# FollowMe.net
KiCad netlist of a schematic drawn in EAGLE
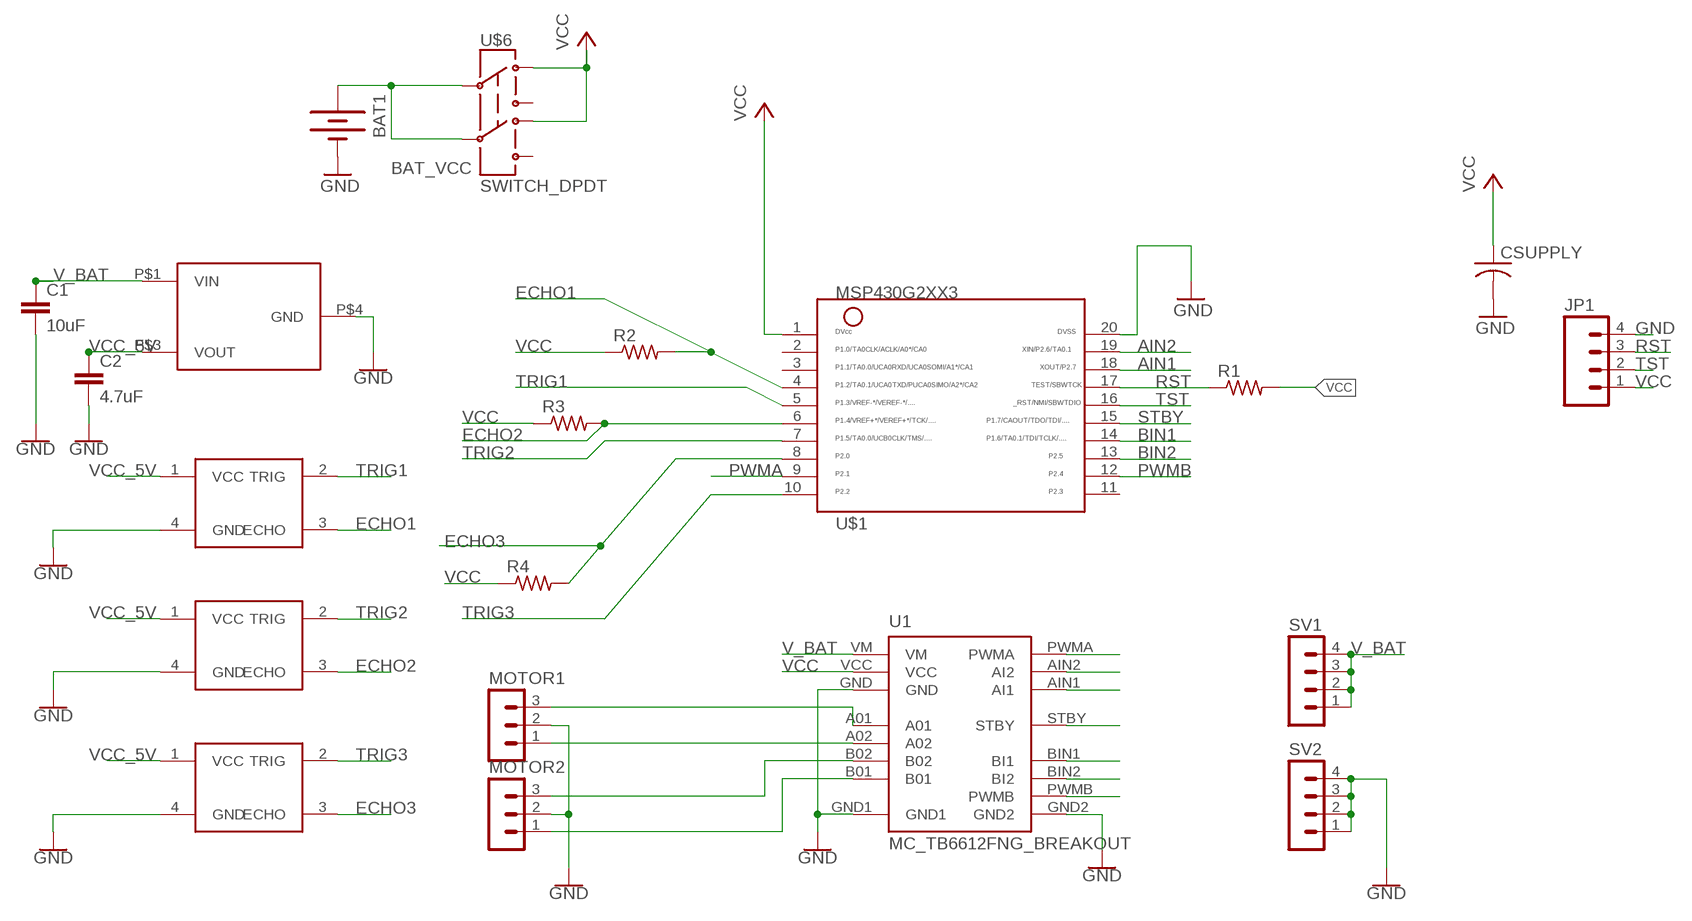
[diagram p0: schematic, sheet 1]

(export (version "E")
  (design (tool "Eeschema 10.0.6"))
  (components
    (comp (ref "BAT1")
      (value "BATTERY")
      (footprint "eagle-import:BATTERY_PACK_2AA")
      (libsource (lib "eagle-import") (part "BATTERY"))
    )
    (comp (ref "C1")
      (value "10uF")
      (footprint "eagle-import:1206")
      (libsource (lib "eagle-import") (part "10UF-1206-6.3V-20%"))
    )
    (comp (ref "C2")
      (value "4.7uF")
      (footprint "eagle-import:1206")
      (libsource (lib "eagle-import") (part "10UF-1206-6.3V-20%"))
    )
    (comp (ref "CSUPPLY")
      (value "C-USC1206")
      (footprint "eagle-import:C1206")
      (libsource (lib "eagle-import") (part "C-USC1206"))
    )
    (comp (ref "JP1")
      (value "M04LOCK")
      (footprint "eagle-import:1X04_LOCK")
      (libsource (lib "eagle-import") (part "M04LOCK"))
    )
    (comp (ref "MOTOR1")
      (value "MA03-1")
      (footprint "eagle-import:MA03-1")
      (libsource (lib "eagle-import") (part "MA03-1"))
    )
    (comp (ref "MOTOR2")
      (value "MA03-1")
      (footprint "eagle-import:MA03-1")
      (libsource (lib "eagle-import") (part "MA03-1"))
    )
    (comp (ref "R1")
      (value "R-US_R1206")
      (footprint "eagle-import:R1206")
      (libsource (lib "eagle-import") (part "R-US_R1206"))
    )
    (comp (ref "R2")
      (value "R-US_R1206")
      (footprint "eagle-import:R1206")
      (libsource (lib "eagle-import") (part "R-US_R1206"))
    )
    (comp (ref "R3")
      (value "R-US_R1206")
      (footprint "eagle-import:R1206")
      (libsource (lib "eagle-import") (part "R-US_R1206"))
    )
    (comp (ref "R4")
      (value "R-US_R1206")
      (footprint "eagle-import:R1206")
      (libsource (lib "eagle-import") (part "R-US_R1206"))
    )
    (comp (ref "SV1")
      (value "MA04-1")
      (footprint "eagle-import:MA04-1")
      (libsource (lib "eagle-import") (part "MA04-1"))
    )
    (comp (ref "SV2")
      (value "MA04-1")
      (footprint "eagle-import:MA04-1")
      (libsource (lib "eagle-import") (part "MA04-1"))
    )
    (comp (ref "U$1")
      (value "MSP430G2XX3TSSOP")
      (footprint "eagle-import:PW20")
      (libsource (lib "eagle-import") (part "MSP430G2XX3TSSOP"))
    )
    (comp (ref "U$2")
      (value "LDO")
      (footprint "eagle-import:LDO")
      (libsource (lib "eagle-import") (part "LDO"))
    )
    (comp (ref "U$3")
      (value "ULTRASONIC")
      (footprint "eagle-import:ULTRASONIC")
      (libsource (lib "eagle-import") (part "ULTRASONIC"))
    )
    (comp (ref "U$4")
      (value "ULTRASONIC")
      (footprint "eagle-import:ULTRASONIC")
      (libsource (lib "eagle-import") (part "ULTRASONIC"))
    )
    (comp (ref "U$5")
      (value "ULTRASONIC")
      (footprint "eagle-import:ULTRASONIC")
      (libsource (lib "eagle-import") (part "ULTRASONIC"))
    )
    (comp (ref "U$6")
      (value "SWITCH_DPDT")
      (footprint "eagle-import:JS_DPDT_TH")
      (libsource (lib "eagle-import") (part "SWITCH_DPDT"))
    )
    (comp (ref "U1")
      (value "MC_TB6612FNG_BREAKOUT")
      (footprint "eagle-import:MC_TB6612FNG")
      (libsource (lib "eagle-import") (part "MC_TB6612FNG_BREAKOUT"))
    )
  )
  (nets
    (net (code "1") (name "/AIN1") (class "Default")
      (node (ref "U$1") (pin "18") (pinfunction "18_18") (pintype "bidirectional"))
      (node (ref "U1") (pin "AIN1") (pinfunction "AI1_AIN1") (pintype "bidirectional"))
    )
    (net (code "2") (name "/AIN2") (class "Default")
      (node (ref "U$1") (pin "19") (pinfunction "19_19") (pintype "bidirectional"))
      (node (ref "U1") (pin "AIN2") (pinfunction "AI2_AIN2") (pintype "bidirectional"))
    )
    (net (code "3") (name "/BAT_VCC") (class "Default")
      (node (ref "BAT1") (pin "3V") (pinfunction "+_3V") (pintype "power_in"))
      (node (ref "U$6") (pin "2") (pinfunction "2_2") (pintype "bidirectional"))
      (node (ref "U$6") (pin "5") (pinfunction "5_5") (pintype "bidirectional"))
    )
    (net (code "4") (name "/BIN1") (class "Default")
      (node (ref "U$1") (pin "14") (pinfunction "14_14") (pintype "bidirectional"))
      (node (ref "U1") (pin "BIN1") (pinfunction "BI1_BIN1") (pintype "bidirectional"))
    )
    (net (code "5") (name "/BIN2") (class "Default")
      (node (ref "U$1") (pin "13") (pinfunction "13_13") (pintype "bidirectional"))
      (node (ref "U1") (pin "BIN2") (pinfunction "BI2_BIN2") (pintype "bidirectional"))
    )
    (net (code "6") (name "/ECHO1") (class "Default")
      (node (ref "R2") (pin "2") (pinfunction "2_2") (pintype "passive"))
      (node (ref "U$1") (pin "4") (pinfunction "4_4") (pintype "bidirectional"))
      (node (ref "U$3") (pin "3") (pinfunction "ECHO_3") (pintype "bidirectional"))
    )
    (net (code "7") (name "/ECHO2") (class "Default")
      (node (ref "R3") (pin "2") (pinfunction "2_2") (pintype "passive"))
      (node (ref "U$1") (pin "6") (pinfunction "6_6") (pintype "bidirectional"))
      (node (ref "U$4") (pin "3") (pinfunction "ECHO_3") (pintype "bidirectional"))
    )
    (net (code "8") (name "/ECHO3") (class "Default")
      (node (ref "R4") (pin "2") (pinfunction "2_2") (pintype "passive"))
      (node (ref "U$1") (pin "8") (pinfunction "8_8") (pintype "bidirectional"))
      (node (ref "U$5") (pin "3") (pinfunction "ECHO_3") (pintype "bidirectional"))
    )
    (net (code "9") (name "/PWMA") (class "Default")
      (node (ref "U$1") (pin "9") (pinfunction "9_9") (pintype "bidirectional"))
      (node (ref "U1") (pin "PWMA") (pinfunction "PWMA_PWMA") (pintype "bidirectional"))
    )
    (net (code "10") (name "/PWMB") (class "Default")
      (node (ref "U$1") (pin "12") (pinfunction "12_12") (pintype "bidirectional"))
      (node (ref "U1") (pin "PWMB") (pinfunction "PWMB_PWMB") (pintype "bidirectional"))
    )
    (net (code "11") (name "/RST") (class "Default")
      (node (ref "JP1") (pin "3") (pinfunction "3_3") (pintype "passive"))
      (node (ref "R1") (pin "1") (pinfunction "1_1") (pintype "passive"))
      (node (ref "U$1") (pin "17") (pinfunction "17_17") (pintype "bidirectional"))
    )
    (net (code "12") (name "/STBY") (class "Default")
      (node (ref "U$1") (pin "15") (pinfunction "15_15") (pintype "bidirectional"))
      (node (ref "U1") (pin "STBY") (pinfunction "STBY_STBY") (pintype "bidirectional"))
    )
    (net (code "13") (name "/TRIG1") (class "Default")
      (node (ref "U$1") (pin "5") (pinfunction "5_5") (pintype "bidirectional"))
      (node (ref "U$3") (pin "2") (pinfunction "TRIG_2") (pintype "bidirectional"))
    )
    (net (code "14") (name "/TRIG2") (class "Default")
      (node (ref "U$1") (pin "7") (pinfunction "7_7") (pintype "bidirectional"))
      (node (ref "U$4") (pin "2") (pinfunction "TRIG_2") (pintype "bidirectional"))
    )
    (net (code "15") (name "/TRIG3") (class "Default")
      (node (ref "U$1") (pin "10") (pinfunction "10_10") (pintype "bidirectional"))
      (node (ref "U$5") (pin "2") (pinfunction "TRIG_2") (pintype "bidirectional"))
    )
    (net (code "16") (name "/TST") (class "Default")
      (node (ref "JP1") (pin "2") (pinfunction "2_2") (pintype "passive"))
      (node (ref "U$1") (pin "16") (pinfunction "16_16") (pintype "bidirectional"))
    )
    (net (code "17") (name "/VCC_5V") (class "Default")
      (node (ref "C2") (pin "1") (pinfunction "1_1") (pintype "passive"))
      (node (ref "U$2") (pin "P$3") (pinfunction "VOUT_P$3") (pintype "bidirectional"))
      (node (ref "U$3") (pin "1") (pinfunction "VCC_1") (pintype "bidirectional"))
      (node (ref "U$4") (pin "1") (pinfunction "VCC_1") (pintype "bidirectional"))
      (node (ref "U$5") (pin "1") (pinfunction "VCC_1") (pintype "bidirectional"))
    )
    (net (code "18") (name "/V_BAT") (class "Default")
      (node (ref "C1") (pin "1") (pinfunction "1_1") (pintype "passive"))
      (node (ref "SV1") (pin "1") (pinfunction "1_1") (pintype "passive"))
      (node (ref "SV1") (pin "2") (pinfunction "2_2") (pintype "passive"))
      (node (ref "SV1") (pin "3") (pinfunction "3_3") (pintype "passive"))
      (node (ref "SV1") (pin "4") (pinfunction "4_4") (pintype "passive"))
      (node (ref "U$2") (pin "P$1") (pinfunction "VIN_P$1") (pintype "bidirectional"))
      (node (ref "U1") (pin "VM") (pinfunction "VM_VM") (pintype "bidirectional"))
    )
    (net (code "19") (name "GND") (class "Default")
      (node (ref "BAT1") (pin "GND") (pinfunction "-_GND") (pintype "power_in"))
      (node (ref "C1") (pin "2") (pinfunction "2_2") (pintype "passive"))
      (node (ref "C2") (pin "2") (pinfunction "2_2") (pintype "passive"))
      (node (ref "CSUPPLY") (pin "2") (pinfunction "2_2") (pintype "passive"))
      (node (ref "JP1") (pin "4") (pinfunction "4_4") (pintype "passive"))
      (node (ref "MOTOR1") (pin "2") (pinfunction "2_2") (pintype "passive"))
      (node (ref "MOTOR2") (pin "2") (pinfunction "2_2") (pintype "passive"))
      (node (ref "SV2") (pin "1") (pinfunction "1_1") (pintype "passive"))
      (node (ref "SV2") (pin "2") (pinfunction "2_2") (pintype "passive"))
      (node (ref "SV2") (pin "3") (pinfunction "3_3") (pintype "passive"))
      (node (ref "SV2") (pin "4") (pinfunction "4_4") (pintype "passive"))
      (node (ref "U$1") (pin "20") (pinfunction "20_20") (pintype "bidirectional"))
      (node (ref "U$2") (pin "P$4") (pinfunction "GND_P$4") (pintype "bidirectional"))
      (node (ref "U$3") (pin "4") (pinfunction "GND_4") (pintype "bidirectional"))
      (node (ref "U$4") (pin "4") (pinfunction "GND_4") (pintype "bidirectional"))
      (node (ref "U$5") (pin "4") (pinfunction "GND_4") (pintype "bidirectional"))
      (node (ref "U1") (pin "GND") (pinfunction "GND_GND") (pintype "bidirectional"))
      (node (ref "U1") (pin "GND1") (pinfunction "GND1_GND1") (pintype "bidirectional"))
      (node (ref "U1") (pin "GND2") (pinfunction "GND2_GND2") (pintype "bidirectional"))
    )
    (net (code "20") (name "Net-(MOTOR1-Pad1)") (class "Default")
      (node (ref "MOTOR1") (pin "1") (pinfunction "1_1") (pintype "passive"))
      (node (ref "U1") (pin "A02") (pinfunction "A02_A02") (pintype "bidirectional"))
    )
    (net (code "21") (name "Net-(MOTOR1-Pad3)") (class "Default")
      (node (ref "MOTOR1") (pin "3") (pinfunction "3_3") (pintype "passive"))
      (node (ref "U1") (pin "A01") (pinfunction "A01_A01") (pintype "bidirectional"))
    )
    (net (code "22") (name "Net-(MOTOR2-Pad1)") (class "Default")
      (node (ref "MOTOR2") (pin "1") (pinfunction "1_1") (pintype "passive"))
      (node (ref "U1") (pin "B01") (pinfunction "B01_B01") (pintype "bidirectional"))
    )
    (net (code "23") (name "Net-(MOTOR2-Pad3)") (class "Default")
      (node (ref "MOTOR2") (pin "3") (pinfunction "3_3") (pintype "passive"))
      (node (ref "U1") (pin "B02") (pinfunction "B02_B02") (pintype "bidirectional"))
    )
    (net (code "24") (name "VCC") (class "Default")
      (node (ref "CSUPPLY") (pin "1") (pinfunction "1_1") (pintype "passive"))
      (node (ref "JP1") (pin "1") (pinfunction "1_1") (pintype "passive"))
      (node (ref "R1") (pin "2") (pinfunction "2_2") (pintype "passive"))
      (node (ref "R2") (pin "1") (pinfunction "1_1") (pintype "passive"))
      (node (ref "R3") (pin "1") (pinfunction "1_1") (pintype "passive"))
      (node (ref "R4") (pin "1") (pinfunction "1_1") (pintype "passive"))
      (node (ref "U$1") (pin "1") (pinfunction "1_1") (pintype "bidirectional"))
      (node (ref "U$6") (pin "1") (pinfunction "1_1") (pintype "bidirectional"))
      (node (ref "U$6") (pin "4") (pinfunction "4_4") (pintype "bidirectional"))
      (node (ref "U1") (pin "VCC") (pinfunction "VCC_VCC") (pintype "bidirectional"))
    )
    (net (code "25") (name "unconnected-(U$1-Pad2)") (class "Default")
      (node (ref "U$1") (pin "2") (pinfunction "2_2") (pintype "bidirectional"))
    )
    (net (code "26") (name "unconnected-(U$1-Pad3)") (class "Default")
      (node (ref "U$1") (pin "3") (pinfunction "3_3") (pintype "bidirectional"))
    )
    (net (code "27") (name "unconnected-(U$1-Pad11)") (class "Default")
      (node (ref "U$1") (pin "11") (pinfunction "11_11") (pintype "bidirectional"))
    )
    (net (code "28") (name "unconnected-(U$6-Pad3)") (class "Default")
      (node (ref "U$6") (pin "3") (pinfunction "3_3") (pintype "bidirectional"))
    )
    (net (code "29") (name "unconnected-(U$6-Pad6)") (class "Default")
      (node (ref "U$6") (pin "6") (pinfunction "6_6") (pintype "bidirectional"))
    )
  )
)
